# board.net
KiCad netlist of a schematic drawn in EAGLE
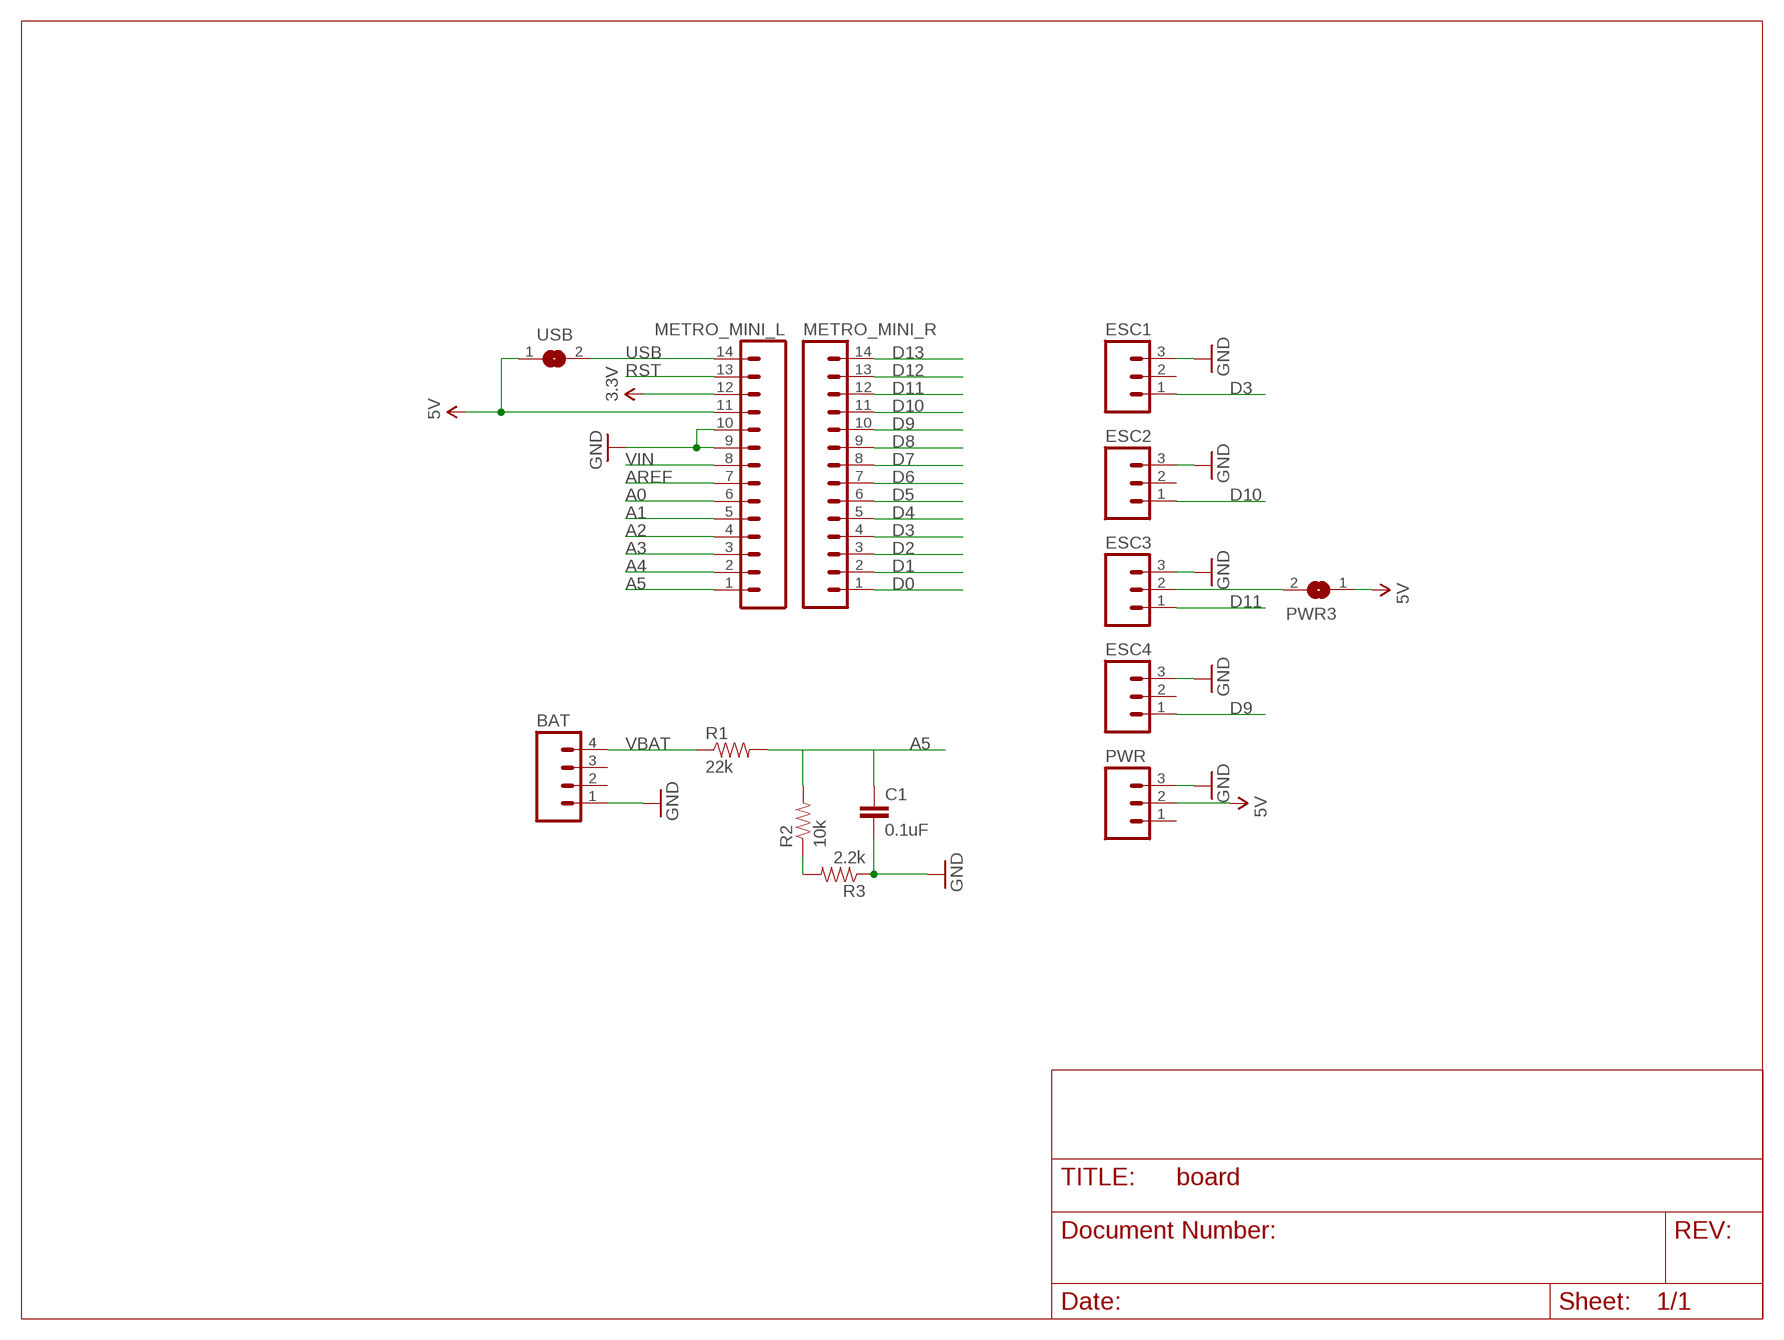
[diagram p0: schematic, sheet 1]

(export (version "E")
  (design (tool "Eeschema 10.0.6"))
  (components
    (comp (ref "BAT")
      (value "M04POLAR")
      (footprint "eagle-import:MOLEX-1X4")
      (libsource (lib "eagle-import") (part "M04POLAR"))
    )
    (comp (ref "C1")
      (value "0.1uF")
      (footprint "eagle-import:AXIAL-5MM")
      (libsource (lib "eagle-import") (part "CAP_"))
    )
    (comp (ref "ESC1")
      (value "M03POLAR")
      (footprint "eagle-import:MOLEX-1X3")
      (libsource (lib "eagle-import") (part "M03POLAR"))
    )
    (comp (ref "ESC2")
      (value "M03POLAR")
      (footprint "eagle-import:MOLEX-1X3")
      (libsource (lib "eagle-import") (part "M03POLAR"))
    )
    (comp (ref "ESC3")
      (value "M03POLAR")
      (footprint "eagle-import:MOLEX-1X3")
      (libsource (lib "eagle-import") (part "M03POLAR"))
    )
    (comp (ref "ESC4")
      (value "M03POLAR")
      (footprint "eagle-import:MOLEX-1X3")
      (libsource (lib "eagle-import") (part "M03POLAR"))
    )
    (comp (ref "METRO_MINI_L")
      (value "M14")
      (footprint "eagle-import:1X14")
      (libsource (lib "eagle-import") (part "M14"))
    )
    (comp (ref "METRO_MINI_R")
      (value "M14")
      (footprint "eagle-import:1X14")
      (libsource (lib "eagle-import") (part "M14"))
    )
    (comp (ref "PWR")
      (value "M03POLAR")
      (footprint "eagle-import:MOLEX-1X3")
      (libsource (lib "eagle-import") (part "M03POLAR"))
    )
    (comp (ref "PWR3")
      (value "SJW")
      (footprint "eagle-import:SJW")
      (libsource (lib "eagle-import") (part "SJW"))
    )
    (comp (ref "R1")
      (value "22k")
      (footprint "eagle-import:AXIAL-0.4")
      (libsource (lib "eagle-import") (part "RESISTORPTH-1/4W"))
    )
    (comp (ref "R2")
      (value "10k")
      (footprint "eagle-import:AXIAL-0.4")
      (libsource (lib "eagle-import") (part "RESISTORPTH-1/4W"))
    )
    (comp (ref "R3")
      (value "2.2k")
      (footprint "eagle-import:AXIAL-0.4")
      (libsource (lib "eagle-import") (part "RESISTORPTH-1/4W"))
    )
    (comp (ref "USB")
      (value "SJW")
      (footprint "eagle-import:SJW")
      (libsource (lib "eagle-import") (part "SJW"))
    )
  )
  (nets
    (net (code "1") (name "/A0") (class "Default")
      (node (ref "METRO_MINI_L") (pin "6") (pinfunction "6_6") (pintype "passive"))
    )
    (net (code "2") (name "/A1") (class "Default")
      (node (ref "METRO_MINI_L") (pin "5") (pinfunction "5_5") (pintype "passive"))
    )
    (net (code "3") (name "/A2") (class "Default")
      (node (ref "METRO_MINI_L") (pin "4") (pinfunction "4_4") (pintype "passive"))
    )
    (net (code "4") (name "/A3") (class "Default")
      (node (ref "METRO_MINI_L") (pin "3") (pinfunction "3_3") (pintype "passive"))
    )
    (net (code "5") (name "/A4") (class "Default")
      (node (ref "METRO_MINI_L") (pin "2") (pinfunction "2_2") (pintype "passive"))
    )
    (net (code "6") (name "/A5") (class "Default")
      (node (ref "C1") (pin "P$1") (pinfunction "1_P$1") (pintype "passive"))
      (node (ref "METRO_MINI_L") (pin "1") (pinfunction "1_1") (pintype "passive"))
      (node (ref "R1") (pin "P$2") (pinfunction "2_P$2") (pintype "passive"))
      (node (ref "R2") (pin "P$2") (pinfunction "2_P$2") (pintype "passive"))
    )
    (net (code "7") (name "/AREF") (class "Default")
      (node (ref "METRO_MINI_L") (pin "7") (pinfunction "7_7") (pintype "passive"))
    )
    (net (code "8") (name "/D0") (class "Default")
      (node (ref "METRO_MINI_R") (pin "1") (pinfunction "1_1") (pintype "passive"))
    )
    (net (code "9") (name "/D1") (class "Default")
      (node (ref "METRO_MINI_R") (pin "2") (pinfunction "2_2") (pintype "passive"))
    )
    (net (code "10") (name "/D2") (class "Default")
      (node (ref "METRO_MINI_R") (pin "3") (pinfunction "3_3") (pintype "passive"))
    )
    (net (code "11") (name "/D3") (class "Default")
      (node (ref "ESC1") (pin "1") (pinfunction "1_1") (pintype "passive"))
      (node (ref "METRO_MINI_R") (pin "4") (pinfunction "4_4") (pintype "passive"))
    )
    (net (code "12") (name "/D4") (class "Default")
      (node (ref "METRO_MINI_R") (pin "5") (pinfunction "5_5") (pintype "passive"))
    )
    (net (code "13") (name "/D5") (class "Default")
      (node (ref "METRO_MINI_R") (pin "6") (pinfunction "6_6") (pintype "passive"))
    )
    (net (code "14") (name "/D6") (class "Default")
      (node (ref "METRO_MINI_R") (pin "7") (pinfunction "7_7") (pintype "passive"))
    )
    (net (code "15") (name "/D7") (class "Default")
      (node (ref "METRO_MINI_R") (pin "8") (pinfunction "8_8") (pintype "passive"))
    )
    (net (code "16") (name "/D8") (class "Default")
      (node (ref "METRO_MINI_R") (pin "9") (pinfunction "9_9") (pintype "passive"))
    )
    (net (code "17") (name "/D9") (class "Default")
      (node (ref "ESC4") (pin "1") (pinfunction "1_1") (pintype "passive"))
      (node (ref "METRO_MINI_R") (pin "10") (pinfunction "10_10") (pintype "passive"))
    )
    (net (code "18") (name "/D10") (class "Default")
      (node (ref "ESC2") (pin "1") (pinfunction "1_1") (pintype "passive"))
      (node (ref "METRO_MINI_R") (pin "11") (pinfunction "11_11") (pintype "passive"))
    )
    (net (code "19") (name "/D11") (class "Default")
      (node (ref "ESC3") (pin "1") (pinfunction "1_1") (pintype "passive"))
      (node (ref "METRO_MINI_R") (pin "12") (pinfunction "12_12") (pintype "passive"))
    )
    (net (code "20") (name "/D12") (class "Default")
      (node (ref "METRO_MINI_R") (pin "13") (pinfunction "13_13") (pintype "passive"))
    )
    (net (code "21") (name "/D13") (class "Default")
      (node (ref "METRO_MINI_R") (pin "14") (pinfunction "14_14") (pintype "passive"))
    )
    (net (code "22") (name "/RST") (class "Default")
      (node (ref "METRO_MINI_L") (pin "13") (pinfunction "13_13") (pintype "passive"))
    )
    (net (code "23") (name "/USB") (class "Default")
      (node (ref "METRO_MINI_L") (pin "14") (pinfunction "14_14") (pintype "passive"))
      (node (ref "USB") (pin "2") (pinfunction "2_2") (pintype "passive"))
    )
    (net (code "24") (name "/VBAT") (class "Default")
      (node (ref "BAT") (pin "4") (pinfunction "4_4") (pintype "passive"))
      (node (ref "R1") (pin "P$1") (pinfunction "1_P$1") (pintype "passive"))
    )
    (net (code "25") (name "/VIN") (class "Default")
      (node (ref "METRO_MINI_L") (pin "8") (pinfunction "8_8") (pintype "passive"))
    )
    (net (code "26") (name "3.3V") (class "Default")
      (node (ref "METRO_MINI_L") (pin "12") (pinfunction "12_12") (pintype "passive"))
    )
    (net (code "27") (name "5V") (class "Default")
      (node (ref "METRO_MINI_L") (pin "11") (pinfunction "11_11") (pintype "passive"))
      (node (ref "PWR") (pin "2") (pinfunction "2_2") (pintype "passive"))
      (node (ref "PWR3") (pin "1") (pinfunction "1_1") (pintype "passive"))
      (node (ref "USB") (pin "1") (pinfunction "1_1") (pintype "passive"))
    )
    (net (code "28") (name "GND") (class "Default")
      (node (ref "BAT") (pin "1") (pinfunction "1_1") (pintype "passive"))
      (node (ref "C1") (pin "P$2") (pinfunction "2_P$2") (pintype "passive"))
      (node (ref "ESC1") (pin "3") (pinfunction "3_3") (pintype "passive"))
      (node (ref "ESC2") (pin "3") (pinfunction "3_3") (pintype "passive"))
      (node (ref "ESC3") (pin "3") (pinfunction "3_3") (pintype "passive"))
      (node (ref "ESC4") (pin "3") (pinfunction "3_3") (pintype "passive"))
      (node (ref "METRO_MINI_L") (pin "10") (pinfunction "10_10") (pintype "passive"))
      (node (ref "METRO_MINI_L") (pin "9") (pinfunction "9_9") (pintype "passive"))
      (node (ref "PWR") (pin "3") (pinfunction "3_3") (pintype "passive"))
      (node (ref "R3") (pin "P$1") (pinfunction "1_P$1") (pintype "passive"))
    )
    (net (code "29") (name "Net-(ESC3-Pad2)") (class "Default")
      (node (ref "ESC3") (pin "2") (pinfunction "2_2") (pintype "passive"))
      (node (ref "PWR3") (pin "2") (pinfunction "2_2") (pintype "passive"))
    )
    (net (code "30") (name "Net-(R2-1)") (class "Default")
      (node (ref "R2") (pin "P$1") (pinfunction "1_P$1") (pintype "passive"))
      (node (ref "R3") (pin "P$2") (pinfunction "2_P$2") (pintype "passive"))
    )
    (net (code "31") (name "unconnected-(BAT-Pad2)") (class "Default")
      (node (ref "BAT") (pin "2") (pinfunction "2_2") (pintype "passive"))
    )
    (net (code "32") (name "unconnected-(BAT-Pad3)") (class "Default")
      (node (ref "BAT") (pin "3") (pinfunction "3_3") (pintype "passive"))
    )
    (net (code "33") (name "unconnected-(ESC1-Pad2)") (class "Default")
      (node (ref "ESC1") (pin "2") (pinfunction "2_2") (pintype "passive"))
    )
    (net (code "34") (name "unconnected-(ESC2-Pad2)") (class "Default")
      (node (ref "ESC2") (pin "2") (pinfunction "2_2") (pintype "passive"))
    )
    (net (code "35") (name "unconnected-(ESC4-Pad2)") (class "Default")
      (node (ref "ESC4") (pin "2") (pinfunction "2_2") (pintype "passive"))
    )
    (net (code "36") (name "unconnected-(PWR-Pad1)") (class "Default")
      (node (ref "PWR") (pin "1") (pinfunction "1_1") (pintype "passive"))
    )
  )
)
